# POWER.net
KiCad netlist of a schematic drawn in Altium Designer
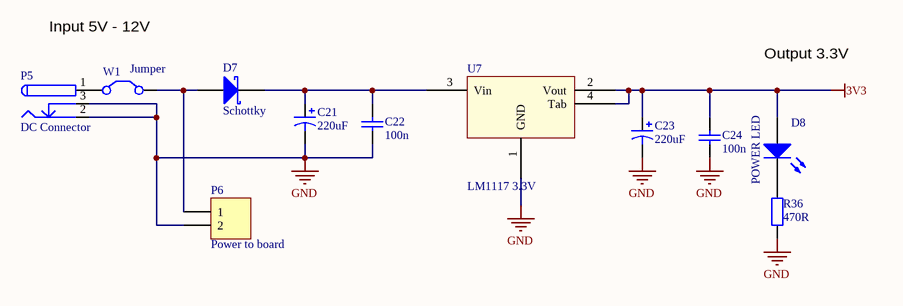
[diagram p0: POWER.SchDoc]

(export (version "E")
  (design (tool "Eeschema 10.0.6"))
  (components
    (comp (ref "C21")
      (value "220uF")
      (footprint "SMD CAPACITOR 220uF")
      (description "Capacitor")
      (fields (field (name "PUBLISHER") "Altium Limited"))
      (libsource (lib "Miscellaneous Devices") (part "Cap Pol1"))
    )
    (comp (ref "C22")
      (value "100n")
      (footprint "1608[0603]")
      (description "Capacitor")
      (fields (field (name "PUBLISHER") "Altium Limited"))
      (libsource (lib "Miscellaneous Devices") (part "Cap"))
    )
    (comp (ref "C23")
      (value "220uF")
      (footprint "SMD CAPACITOR 220uF")
      (description "Capacitor")
      (fields (field (name "PUBLISHER") "Altium Limited"))
      (libsource (lib "Miscellaneous Devices") (part "Cap Pol1"))
    )
    (comp (ref "C24")
      (value "100n")
      (footprint "1608[0603]")
      (description "Capacitor")
      (fields (field (name "PUBLISHER") "Altium Limited"))
      (libsource (lib "Miscellaneous Devices") (part "Cap"))
    )
    (comp (ref "D7")
      (value "Schottky")
      (footprint "SMB")
      (description "Schottky Diode")
      (fields (field (name "PUBLISHER") "Altium Limited"))
      (libsource (lib "Miscellaneous Devices") (part "D Schottky"))
    )
    (comp (ref "D8")
      (value "POWER LED")
      (footprint "LED-1")
      (description "Typical INFRARED GaAs LED")
      (fields (field (name "PUBLISHER") "Altium Limited"))
      (libsource (lib "Miscellaneous Devices") (part "LED0"))
    )
    (comp (ref "P5")
      (value "DC Connector")
      (footprint "DC Connector")
      (description "DC Power Connector")
      (libsource (lib "LukaLIBRARY") (part "DC Connector"))
    )
    (comp (ref "P6")
      (value "Power to board")
      (footprint "Block2 - 3.81")
      (description "Header, 2-Pin")
      (fields (field (name "PUBLISHER") "Altium Limited"))
      (libsource (lib "Miscellaneous Connectors") (part "Header 2"))
    )
    (comp (ref "R36")
      (value "470R")
      (footprint "1608[0603]")
      (description "Resistor")
      (fields (field (name "PUBLISHER") "Altium Limited"))
      (libsource (lib "Miscellaneous Devices") (part "Res2"))
    )
    (comp (ref "U7")
      (value "LM1117 3.3V")
      (footprint "TO220")
      (description "Voltage Regulator")
      (libsource (lib "LukaLIBRARY") (part "LM1117"))
    )
    (comp (ref "W1")
      (value "Jumper")
      (footprint "HDR1X2")
      (description "Jumper Wire")
      (fields (field (name "PUBLISHER") "Altium Limited"))
      (libsource (lib "Miscellaneous Devices") (part "Jumper"))
    )
  )
  (nets
    (net (code "1") (name "3V3") (class "Default")
      (node (ref "C23") (pin "1") (pinfunction "1_1") (pintype "passive"))
      (node (ref "C24") (pin "1") (pinfunction "1_1") (pintype "passive"))
      (node (ref "D8") (pin "1") (pinfunction "A_1") (pintype "passive"))
      (node (ref "U7") (pin "2") (pinfunction "Vout_2") (pintype "passive"))
      (node (ref "U7") (pin "4") (pinfunction "Tab_4") (pintype "passive"))
    )
    (net (code "2") (name "GND") (class "Default")
      (node (ref "C21") (pin "2") (pinfunction "2_2") (pintype "passive"))
      (node (ref "C22") (pin "2") (pinfunction "2_2") (pintype "passive"))
      (node (ref "C23") (pin "2") (pinfunction "2_2") (pintype "passive"))
      (node (ref "C24") (pin "2") (pinfunction "2_2") (pintype "passive"))
      (node (ref "P5") (pin "2") (pinfunction "2_2") (pintype "power_in"))
      (node (ref "P5") (pin "3") (pinfunction "3_3") (pintype "power_in"))
      (node (ref "P6") (pin "2") (pinfunction "2_2") (pintype "passive"))
      (node (ref "R36") (pin "1") (pinfunction "1_1") (pintype "passive"))
      (node (ref "U7") (pin "1") (pinfunction "GND_1") (pintype "passive"))
    )
    (net (code "3") (name "Net-(D7-A)") (class "Default")
      (node (ref "D7") (pin "1") (pinfunction "A_1") (pintype "passive"))
      (node (ref "P6") (pin "1") (pinfunction "1_1") (pintype "passive"))
      (node (ref "W1") (pin "2") (pinfunction "C2_2") (pintype "passive"))
    )
    (net (code "4") (name "Net-(D7-K)") (class "Default")
      (node (ref "C21") (pin "1") (pinfunction "1_1") (pintype "passive"))
      (node (ref "C22") (pin "1") (pinfunction "1_1") (pintype "passive"))
      (node (ref "D7") (pin "2") (pinfunction "K_2") (pintype "passive"))
      (node (ref "U7") (pin "3") (pinfunction "Vin_3") (pintype "passive"))
    )
    (net (code "5") (name "Net-(D8-K)") (class "Default")
      (node (ref "D8") (pin "2") (pinfunction "K_2") (pintype "passive"))
      (node (ref "R36") (pin "2") (pinfunction "2_2") (pintype "passive"))
    )
    (net (code "6") (name "Net-(W1-C1)") (class "Default")
      (node (ref "P5") (pin "1") (pinfunction "1_1") (pintype "power_in"))
      (node (ref "W1") (pin "1") (pinfunction "C1_1") (pintype "passive"))
    )
  )
)
